# Modem_rev_a1.net
KiCad netlist of a schematic drawn in EAGLE
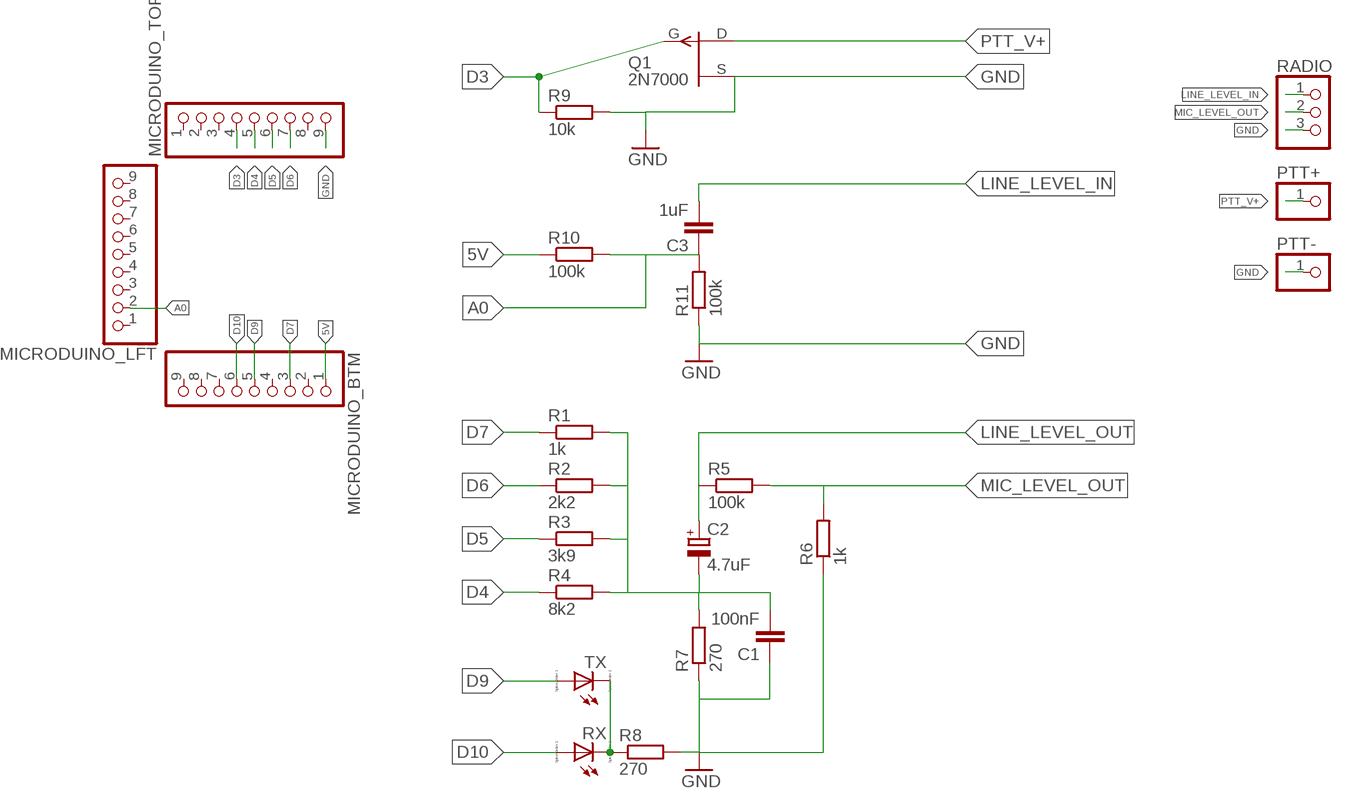
[diagram p0: schematic, sheet 1]

(export (version "E")
  (design (tool "Eeschema 10.0.6"))
  (components
    (comp (ref "C1")
      (value "100nF")
      (footprint "eagle-import:C2.5-2")
      (libsource (lib "eagle-import") (part "C2.5/2"))
    )
    (comp (ref "C2")
      (value "4.7uF")
      (footprint "eagle-import:E2,5-4R")
      (libsource (lib "eagle-import") (part "CPOL-EUE2.5-5V"))
    )
    (comp (ref "C3")
      (value "1uF")
      (footprint "eagle-import:C2.5-2")
      (libsource (lib "eagle-import") (part "C2.5/2"))
    )
    (comp (ref "MICRODUINO_BTM")
      (value "PINHD-1X9")
      (footprint "eagle-import:1X09-MICRODUINO")
      (libsource (lib "eagle-import") (part "PINHD-1X9"))
    )
    (comp (ref "MICRODUINO_LFT")
      (value "PINHD-1X9")
      (footprint "eagle-import:1X09-MICRODUINO")
      (libsource (lib "eagle-import") (part "PINHD-1X9"))
    )
    (comp (ref "MICRODUINO_TOP")
      (value "PINHD-1X9")
      (footprint "eagle-import:1X09-MICRODUINO")
      (libsource (lib "eagle-import") (part "PINHD-1X9"))
    )
    (comp (ref "PTT+")
      (value "PINHD-1X1")
      (footprint "eagle-import:1X01")
      (libsource (lib "eagle-import") (part "PINHD-1X1"))
    )
    (comp (ref "PTT-")
      (value "PINHD-1X1")
      (footprint "eagle-import:1X01")
      (libsource (lib "eagle-import") (part "PINHD-1X1"))
    )
    (comp (ref "Q1")
      (value "2N7000")
      (footprint "eagle-import:TO92_MOD")
      (libsource (lib "eagle-import") (part "2N3820"))
    )
    (comp (ref "R1")
      (value "1k")
      (footprint "eagle-import:0204V")
      (libsource (lib "eagle-import") (part "resistor_R-EU_0204/2V"))
    )
    (comp (ref "R2")
      (value "2k2")
      (footprint "eagle-import:0204V")
      (libsource (lib "eagle-import") (part "resistor_R-EU_0204/2V"))
    )
    (comp (ref "R3")
      (value "3k9")
      (footprint "eagle-import:0204V")
      (libsource (lib "eagle-import") (part "resistor_R-EU_0204/2V"))
    )
    (comp (ref "R4")
      (value "8k2")
      (footprint "eagle-import:0204V")
      (libsource (lib "eagle-import") (part "resistor_R-EU_0204/2V"))
    )
    (comp (ref "R5")
      (value "100k")
      (footprint "eagle-import:0204V")
      (libsource (lib "eagle-import") (part "resistor_R-EU_0204/2V"))
    )
    (comp (ref "R6")
      (value "1k")
      (footprint "eagle-import:0204V")
      (libsource (lib "eagle-import") (part "resistor_R-EU_0204/2V"))
    )
    (comp (ref "R7")
      (value "270")
      (footprint "eagle-import:0204V")
      (libsource (lib "eagle-import") (part "resistor_R-EU_0204/2V"))
    )
    (comp (ref "R8")
      (value "270")
      (footprint "eagle-import:0204V")
      (libsource (lib "eagle-import") (part "resistor_R-EU_0204/2V"))
    )
    (comp (ref "R9")
      (value "10k")
      (footprint "eagle-import:0204V")
      (libsource (lib "eagle-import") (part "R-EU_0204/2V"))
    )
    (comp (ref "R10")
      (value "100k")
      (footprint "eagle-import:0204V")
      (libsource (lib "eagle-import") (part "R-EU_0204/2V"))
    )
    (comp (ref "R11")
      (value "100k")
      (footprint "eagle-import:0204V")
      (libsource (lib "eagle-import") (part "R-EU_0204/2V"))
    )
    (comp (ref "RADIO")
      (value "PINHD-1X3")
      (footprint "eagle-import:1X03")
      (libsource (lib "eagle-import") (part "PINHD-1X3"))
    )
    (comp (ref "RX")
      (value "LED_ELD260")
      (footprint "eagle-import:LED_LD260")
      (libsource (lib "eagle-import") (part "LED_ELD260"))
    )
    (comp (ref "TX")
      (value "LED_ELD260")
      (footprint "eagle-import:LED_LD260")
      (libsource (lib "eagle-import") (part "LED_ELD260"))
    )
  )
  (nets
    (net (code "1") (name "5V") (class "Default")
      (node (ref "MICRODUINO_BTM") (pin "1") (pinfunction "1_1") (pintype "passive"))
      (node (ref "R10") (pin "1") (pinfunction "1_1") (pintype "passive"))
    )
    (net (code "2") (name "A0") (class "Default")
      (node (ref "C3") (pin "1") (pinfunction "1_1") (pintype "passive"))
      (node (ref "MICRODUINO_LFT") (pin "2") (pinfunction "2_2") (pintype "passive"))
      (node (ref "R10") (pin "2") (pinfunction "2_2") (pintype "passive"))
      (node (ref "R11") (pin "2") (pinfunction "2_2") (pintype "passive"))
    )
    (net (code "3") (name "D3") (class "Default")
      (node (ref "MICRODUINO_TOP") (pin "4") (pinfunction "4_4") (pintype "passive"))
      (node (ref "Q1") (pin "2") (pinfunction "G_2") (pintype "passive"))
      (node (ref "R9") (pin "1") (pinfunction "1_1") (pintype "passive"))
    )
    (net (code "4") (name "D4") (class "Default")
      (node (ref "MICRODUINO_TOP") (pin "5") (pinfunction "5_5") (pintype "passive"))
      (node (ref "R4") (pin "1") (pinfunction "1_1") (pintype "passive"))
    )
    (net (code "5") (name "D5") (class "Default")
      (node (ref "MICRODUINO_TOP") (pin "6") (pinfunction "6_6") (pintype "passive"))
      (node (ref "R3") (pin "1") (pinfunction "1_1") (pintype "passive"))
    )
    (net (code "6") (name "D6") (class "Default")
      (node (ref "MICRODUINO_TOP") (pin "7") (pinfunction "7_7") (pintype "passive"))
      (node (ref "R2") (pin "1") (pinfunction "1_1") (pintype "passive"))
    )
    (net (code "7") (name "D7") (class "Default")
      (node (ref "MICRODUINO_BTM") (pin "3") (pinfunction "3_3") (pintype "passive"))
      (node (ref "R1") (pin "1") (pinfunction "1_1") (pintype "passive"))
    )
    (net (code "8") (name "D9") (class "Default")
      (node (ref "MICRODUINO_BTM") (pin "5") (pinfunction "5_5") (pintype "passive"))
      (node (ref "TX") (pin "A") (pinfunction "A_A") (pintype "passive"))
    )
    (net (code "9") (name "D10") (class "Default")
      (node (ref "MICRODUINO_BTM") (pin "6") (pinfunction "6_6") (pintype "passive"))
      (node (ref "RX") (pin "A") (pinfunction "A_A") (pintype "passive"))
    )
    (net (code "10") (name "GND") (class "Default")
      (node (ref "C1") (pin "1") (pinfunction "1_1") (pintype "passive"))
      (node (ref "MICRODUINO_TOP") (pin "9") (pinfunction "9_9") (pintype "passive"))
      (node (ref "PTT-") (pin "1") (pinfunction "1_1") (pintype "passive"))
      (node (ref "Q1") (pin "3") (pinfunction "D_3") (pintype "passive"))
      (node (ref "R11") (pin "1") (pinfunction "1_1") (pintype "passive"))
      (node (ref "R6") (pin "1") (pinfunction "1_1") (pintype "passive"))
      (node (ref "R7") (pin "1") (pinfunction "1_1") (pintype "passive"))
      (node (ref "R8") (pin "2") (pinfunction "2_2") (pintype "passive"))
      (node (ref "R9") (pin "2") (pinfunction "2_2") (pintype "passive"))
      (node (ref "RADIO") (pin "3") (pinfunction "3_3") (pintype "passive"))
    )
    (net (code "11") (name "LINE_LEVEL_IN") (class "Default")
      (node (ref "C3") (pin "2") (pinfunction "2_2") (pintype "passive"))
      (node (ref "RADIO") (pin "1") (pinfunction "1_1") (pintype "passive"))
    )
    (net (code "12") (name "LINE_LEVEL_OUT") (class "Default")
      (node (ref "C2") (pin "+") (pinfunction "+_+") (pintype "passive"))
      (node (ref "R5") (pin "1") (pinfunction "1_1") (pintype "passive"))
    )
    (net (code "13") (name "MIC_LEVEL_OUT") (class "Default")
      (node (ref "R5") (pin "2") (pinfunction "2_2") (pintype "passive"))
      (node (ref "R6") (pin "2") (pinfunction "2_2") (pintype "passive"))
      (node (ref "RADIO") (pin "2") (pinfunction "2_2") (pintype "passive"))
    )
    (net (code "14") (name "Net-(C1-Pad2)") (class "Default")
      (node (ref "C1") (pin "2") (pinfunction "2_2") (pintype "passive"))
      (node (ref "C2") (pin "-") (pinfunction "-_-") (pintype "passive"))
      (node (ref "R1") (pin "2") (pinfunction "2_2") (pintype "passive"))
      (node (ref "R2") (pin "2") (pinfunction "2_2") (pintype "passive"))
      (node (ref "R3") (pin "2") (pinfunction "2_2") (pintype "passive"))
      (node (ref "R4") (pin "2") (pinfunction "2_2") (pintype "passive"))
      (node (ref "R7") (pin "2") (pinfunction "2_2") (pintype "passive"))
    )
    (net (code "15") (name "Net-(RX-C)") (class "Default")
      (node (ref "R8") (pin "1") (pinfunction "1_1") (pintype "passive"))
      (node (ref "RX") (pin "K") (pinfunction "C_K") (pintype "passive"))
      (node (ref "TX") (pin "K") (pinfunction "C_K") (pintype "passive"))
    )
    (net (code "16") (name "PTT_V+") (class "Default")
      (node (ref "PTT+") (pin "1") (pinfunction "1_1") (pintype "passive"))
      (node (ref "Q1") (pin "1") (pinfunction "S_1") (pintype "passive"))
    )
    (net (code "17") (name "unconnected-(MICRODUINO_BTM-Pad2)") (class "Default")
      (node (ref "MICRODUINO_BTM") (pin "2") (pinfunction "2_2") (pintype "passive"))
    )
    (net (code "18") (name "unconnected-(MICRODUINO_BTM-Pad4)") (class "Default")
      (node (ref "MICRODUINO_BTM") (pin "4") (pinfunction "4_4") (pintype "passive"))
    )
    (net (code "19") (name "unconnected-(MICRODUINO_BTM-Pad7)") (class "Default")
      (node (ref "MICRODUINO_BTM") (pin "7") (pinfunction "7_7") (pintype "passive"))
    )
    (net (code "20") (name "unconnected-(MICRODUINO_BTM-Pad8)") (class "Default")
      (node (ref "MICRODUINO_BTM") (pin "8") (pinfunction "8_8") (pintype "passive"))
    )
    (net (code "21") (name "unconnected-(MICRODUINO_BTM-Pad9)") (class "Default")
      (node (ref "MICRODUINO_BTM") (pin "9") (pinfunction "9_9") (pintype "passive"))
    )
    (net (code "22") (name "unconnected-(MICRODUINO_LFT-Pad1)") (class "Default")
      (node (ref "MICRODUINO_LFT") (pin "1") (pinfunction "1_1") (pintype "passive"))
    )
    (net (code "23") (name "unconnected-(MICRODUINO_LFT-Pad3)") (class "Default")
      (node (ref "MICRODUINO_LFT") (pin "3") (pinfunction "3_3") (pintype "passive"))
    )
    (net (code "24") (name "unconnected-(MICRODUINO_LFT-Pad4)") (class "Default")
      (node (ref "MICRODUINO_LFT") (pin "4") (pinfunction "4_4") (pintype "passive"))
    )
    (net (code "25") (name "unconnected-(MICRODUINO_LFT-Pad5)") (class "Default")
      (node (ref "MICRODUINO_LFT") (pin "5") (pinfunction "5_5") (pintype "passive"))
    )
    (net (code "26") (name "unconnected-(MICRODUINO_LFT-Pad6)") (class "Default")
      (node (ref "MICRODUINO_LFT") (pin "6") (pinfunction "6_6") (pintype "passive"))
    )
    (net (code "27") (name "unconnected-(MICRODUINO_LFT-Pad7)") (class "Default")
      (node (ref "MICRODUINO_LFT") (pin "7") (pinfunction "7_7") (pintype "passive"))
    )
    (net (code "28") (name "unconnected-(MICRODUINO_LFT-Pad8)") (class "Default")
      (node (ref "MICRODUINO_LFT") (pin "8") (pinfunction "8_8") (pintype "passive"))
    )
    (net (code "29") (name "unconnected-(MICRODUINO_LFT-Pad9)") (class "Default")
      (node (ref "MICRODUINO_LFT") (pin "9") (pinfunction "9_9") (pintype "passive"))
    )
    (net (code "30") (name "unconnected-(MICRODUINO_TOP-Pad1)") (class "Default")
      (node (ref "MICRODUINO_TOP") (pin "1") (pinfunction "1_1") (pintype "passive"))
    )
    (net (code "31") (name "unconnected-(MICRODUINO_TOP-Pad2)") (class "Default")
      (node (ref "MICRODUINO_TOP") (pin "2") (pinfunction "2_2") (pintype "passive"))
    )
    (net (code "32") (name "unconnected-(MICRODUINO_TOP-Pad3)") (class "Default")
      (node (ref "MICRODUINO_TOP") (pin "3") (pinfunction "3_3") (pintype "passive"))
    )
    (net (code "33") (name "unconnected-(MICRODUINO_TOP-Pad8)") (class "Default")
      (node (ref "MICRODUINO_TOP") (pin "8") (pinfunction "8_8") (pintype "passive"))
    )
  )
)
